# Buffers.net
KiCad netlist of a schematic drawn in Altium Designer
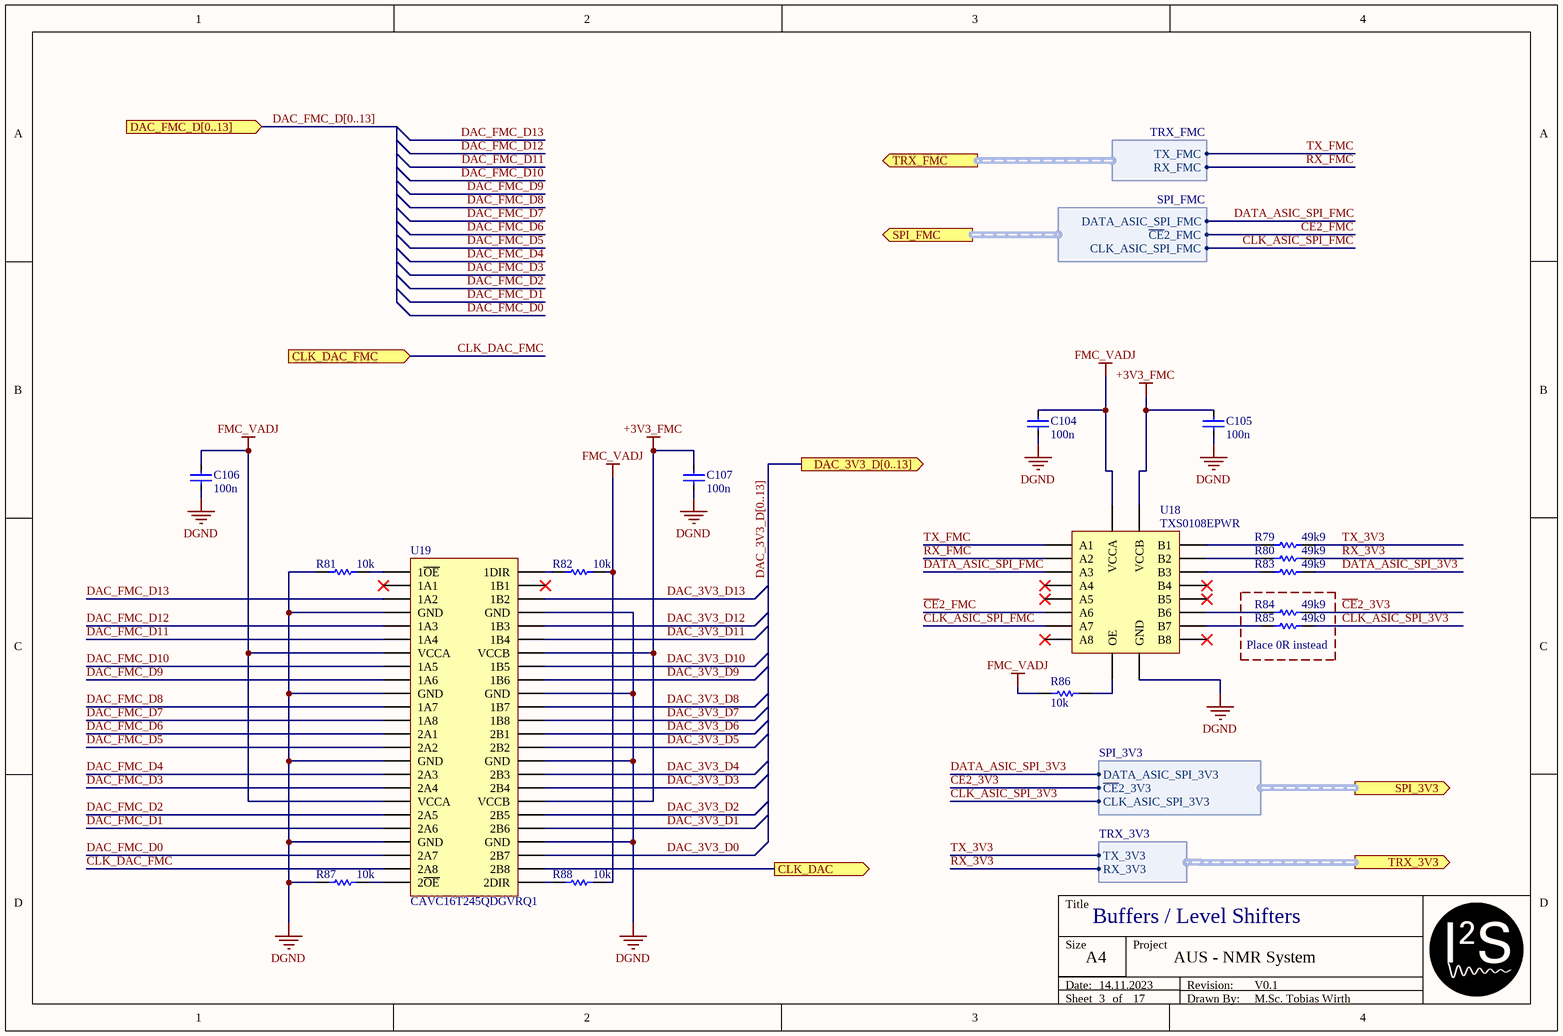
[diagram p0: Buffers.SchDoc]

(export (version "E")
  (design (tool "Eeschema 10.0.6"))
  (components
    (comp (ref "C104") (value "100n") (footprint "CAP_0402") (libsource (lib "IIS-Lib_TW") (part "Cap")))
    (comp (ref "C105") (value "100n") (footprint "CAP_0402") (libsource (lib "IIS-Lib_TW") (part "Cap")))
    (comp (ref "C106") (value "100n") (footprint "CAP_0402") (libsource (lib "IIS-Lib_TW") (part "Cap")))
    (comp (ref "C107") (value "100n") (footprint "CAP_0402") (libsource (lib "IIS-Lib_TW") (part "Cap")))
    (comp (ref "R79") (value "49k9") (footprint "RES_0402") (libsource (lib "IIS-Lib_TW") (part "Res")))
    (comp (ref "R80") (value "49k9") (footprint "RES_0402") (libsource (lib "IIS-Lib_TW") (part "Res")))
    (comp (ref "R81") (value "10k") (footprint "RES_0402") (libsource (lib "IIS-Lib_TW") (part "Res")))
    (comp (ref "R82") (value "10k") (footprint "RES_0402") (libsource (lib "IIS-Lib_TW") (part "Res")))
    (comp (ref "R83") (value "49k9") (footprint "RES_0402") (libsource (lib "IIS-Lib_TW") (part "Res")))
    (comp (ref "R84") (value "49k9") (footprint "RES_0402") (libsource (lib "IIS-Lib_TW") (part "Res")))
    (comp (ref "R85") (value "49k9") (footprint "RES_0402") (libsource (lib "IIS-Lib_TW") (part "Res")))
    (comp (ref "R86") (value "10k") (footprint "RES_0402") (libsource (lib "IIS-Lib_TW") (part "Res")))
    (comp (ref "R87") (value "10k") (footprint "RES_0402") (libsource (lib "IIS-Lib_TW") (part "Res")))
    (comp (ref "R88") (value "10k") (footprint "RES_0402") (libsource (lib "IIS-Lib_TW") (part "Res")))
    (comp (ref "U18")
      (value "TXS0108EPWR")
      (footprint "TSSOP-20")
      (description "8-Bit Bi-directional, Level-Shifting, Voltage Translator for Open-Drain and Push-Pull Applications")
      (libsource (lib "IIS-Lib_TW") (part "TXS0108EPWR"))
    )
    (comp (ref "U19")
      (value "CAVC16T245QDGVRQ1")
      (footprint "IIS-Lib_TW:TSSOP40P640X120-48N")
      (description "16-Bit Dual-Supply Bus Transceiver With Configurable Voltage Translation and 3-State Outputs")
      (libsource (lib "IIS-Lib_TW") (part "CAVC16T245QDGVRQ1"))
    )
  )
  (nets
    (net (code "5") (name "+3V3_FMC") (class "Default")
      (node (ref "C105") (pin "1") (pinfunction "1_1") (pintype "passive"))
      (node (ref "C107") (pin "1") (pinfunction "1_1") (pintype "passive"))
      (node (ref "U18") (pin "19") (pinfunction "VCCB_19") (pintype "passive"))
      (node (ref "U19") (pin "18") (pinfunction "VCCB_18") (pintype "passive"))
      (node (ref "U19") (pin "7") (pinfunction "VCCB_7") (pintype "passive"))
    )
    (net (code "6") (name "/CLK_ASIC_SPI_3V3") (class "Default")
      (node (ref "R85") (pin "2") (pinfunction "2_2") (pintype "passive"))
    )
    (net (code "7") (name "/CLK_ASIC_SPI_FMC") (class "Default")
      (node (ref "U18") (pin "8") (pinfunction "A7_8") (pintype "passive"))
    )
    (net (code "8") (name "/CLK_DAC") (class "Default")
      (node (ref "U19") (pin "23") (pinfunction "2B8_23") (pintype "passive"))
    )
    (net (code "9") (name "/CLK_DAC_FMC") (class "Default")
      (node (ref "U19") (pin "26") (pinfunction "2A8_26") (pintype "passive"))
    )
    (net (code "10") (name "/DAC_3V3_D0") (class "Default")
      (node (ref "U19") (pin "22") (pinfunction "2B7_22") (pintype "passive"))
    )
    (net (code "11") (name "/DAC_3V3_D1") (class "Default")
      (node (ref "U19") (pin "20") (pinfunction "2B6_20") (pintype "passive"))
    )
    (net (code "12") (name "/DAC_3V3_D2") (class "Default")
      (node (ref "U19") (pin "19") (pinfunction "2B5_19") (pintype "passive"))
    )
    (net (code "13") (name "/DAC_3V3_D3") (class "Default")
      (node (ref "U19") (pin "17") (pinfunction "2B4_17") (pintype "passive"))
    )
    (net (code "14") (name "/DAC_3V3_D4") (class "Default")
      (node (ref "U19") (pin "16") (pinfunction "2B3_16") (pintype "passive"))
    )
    (net (code "15") (name "/DAC_3V3_D5") (class "Default")
      (node (ref "U19") (pin "14") (pinfunction "2B2_14") (pintype "passive"))
    )
    (net (code "16") (name "/DAC_3V3_D6") (class "Default")
      (node (ref "U19") (pin "13") (pinfunction "2B1_13") (pintype "passive"))
    )
    (net (code "17") (name "/DAC_3V3_D7") (class "Default")
      (node (ref "U19") (pin "12") (pinfunction "1B8_12") (pintype "passive"))
    )
    (net (code "18") (name "/DAC_3V3_D8") (class "Default")
      (node (ref "U19") (pin "11") (pinfunction "1B7_11") (pintype "passive"))
    )
    (net (code "19") (name "/DAC_3V3_D9") (class "Default")
      (node (ref "U19") (pin "9") (pinfunction "1B6_9") (pintype "passive"))
    )
    (net (code "20") (name "/DAC_3V3_D10") (class "Default")
      (node (ref "U19") (pin "8") (pinfunction "1B5_8") (pintype "passive"))
    )
    (net (code "21") (name "/DAC_3V3_D11") (class "Default")
      (node (ref "U19") (pin "6") (pinfunction "1B4_6") (pintype "passive"))
    )
    (net (code "22") (name "/DAC_3V3_D12") (class "Default")
      (node (ref "U19") (pin "5") (pinfunction "1B3_5") (pintype "passive"))
    )
    (net (code "23") (name "/DAC_3V3_D13") (class "Default")
      (node (ref "U19") (pin "3") (pinfunction "1B2_3") (pintype "passive"))
    )
    (net (code "25") (name "/DAC_FMC_D0") (class "Default")
      (node (ref "U19") (pin "27") (pinfunction "2A7_27") (pintype "passive"))
    )
    (net (code "26") (name "/DAC_FMC_D1") (class "Default")
      (node (ref "U19") (pin "29") (pinfunction "2A6_29") (pintype "passive"))
    )
    (net (code "27") (name "/DAC_FMC_D2") (class "Default")
      (node (ref "U19") (pin "30") (pinfunction "2A5_30") (pintype "passive"))
    )
    (net (code "28") (name "/DAC_FMC_D3") (class "Default")
      (node (ref "U19") (pin "32") (pinfunction "2A4_32") (pintype "passive"))
    )
    (net (code "29") (name "/DAC_FMC_D4") (class "Default")
      (node (ref "U19") (pin "33") (pinfunction "2A3_33") (pintype "passive"))
    )
    (net (code "30") (name "/DAC_FMC_D5") (class "Default")
      (node (ref "U19") (pin "35") (pinfunction "2A2_35") (pintype "passive"))
    )
    (net (code "31") (name "/DAC_FMC_D6") (class "Default")
      (node (ref "U19") (pin "36") (pinfunction "2A1_36") (pintype "passive"))
    )
    (net (code "32") (name "/DAC_FMC_D7") (class "Default")
      (node (ref "U19") (pin "37") (pinfunction "1A8_37") (pintype "passive"))
    )
    (net (code "33") (name "/DAC_FMC_D8") (class "Default")
      (node (ref "U19") (pin "38") (pinfunction "1A7_38") (pintype "passive"))
    )
    (net (code "34") (name "/DAC_FMC_D9") (class "Default")
      (node (ref "U19") (pin "40") (pinfunction "1A6_40") (pintype "passive"))
    )
    (net (code "35") (name "/DAC_FMC_D10") (class "Default")
      (node (ref "U19") (pin "41") (pinfunction "1A5_41") (pintype "passive"))
    )
    (net (code "36") (name "/DAC_FMC_D11") (class "Default")
      (node (ref "U19") (pin "43") (pinfunction "1A4_43") (pintype "passive"))
    )
    (net (code "37") (name "/DAC_FMC_D12") (class "Default")
      (node (ref "U19") (pin "44") (pinfunction "1A3_44") (pintype "passive"))
    )
    (net (code "38") (name "/DAC_FMC_D13") (class "Default")
      (node (ref "U19") (pin "46") (pinfunction "1A2_46") (pintype "passive"))
    )
    (net (code "40") (name "/DATA_ASIC_SPI_3V3") (class "Default")
      (node (ref "R83") (pin "2") (pinfunction "2_2") (pintype "passive"))
    )
    (net (code "41") (name "/DATA_ASIC_SPI_FMC") (class "Default")
      (node (ref "U18") (pin "4") (pinfunction "A3_4") (pintype "passive"))
    )
    (net (code "42") (name "/RX_3V3") (class "Default")
      (node (ref "R80") (pin "2") (pinfunction "2_2") (pintype "passive"))
    )
    (net (code "43") (name "/RX_FMC") (class "Default")
      (node (ref "U18") (pin "3") (pinfunction "A2_3") (pintype "passive"))
    )
    (net (code "44") (name "/TX_3V3") (class "Default")
      (node (ref "R79") (pin "2") (pinfunction "2_2") (pintype "passive"))
    )
    (net (code "45") (name "/TX_FMC") (class "Default")
      (node (ref "U18") (pin "1") (pinfunction "A1_1") (pintype "passive"))
    )
    (net (code "50") (name "/~{CE}2_3V3") (class "Default")
      (node (ref "R84") (pin "2") (pinfunction "2_2") (pintype "passive"))
    )
    (net (code "51") (name "/~{CE}2_FMC") (class "Default")
      (node (ref "U18") (pin "7") (pinfunction "A6_7") (pintype "passive"))
    )
    (net (code "52") (name "DGND") (class "Default")
      (node (ref "C104") (pin "2") (pinfunction "2_2") (pintype "passive"))
      (node (ref "C105") (pin "2") (pinfunction "2_2") (pintype "passive"))
      (node (ref "C106") (pin "2") (pinfunction "2_2") (pintype "passive"))
      (node (ref "C107") (pin "2") (pinfunction "2_2") (pintype "passive"))
      (node (ref "R81") (pin "2") (pinfunction "2_2") (pintype "passive"))
      (node (ref "R87") (pin "2") (pinfunction "2_2") (pintype "passive"))
      (node (ref "U18") (pin "11") (pinfunction "GND_11") (pintype "passive"))
      (node (ref "U19") (pin "10") (pinfunction "GND_10") (pintype "passive"))
      (node (ref "U19") (pin "15") (pinfunction "GND_15") (pintype "passive"))
      (node (ref "U19") (pin "21") (pinfunction "GND_21") (pintype "passive"))
      (node (ref "U19") (pin "28") (pinfunction "GND_28") (pintype "passive"))
      (node (ref "U19") (pin "34") (pinfunction "GND_34") (pintype "passive"))
      (node (ref "U19") (pin "39") (pinfunction "GND_39") (pintype "passive"))
      (node (ref "U19") (pin "4") (pinfunction "GND_4") (pintype "passive"))
      (node (ref "U19") (pin "45") (pinfunction "GND_45") (pintype "passive"))
    )
    (net (code "53") (name "FMC_VADJ") (class "Default")
      (node (ref "C104") (pin "1") (pinfunction "1_1") (pintype "passive"))
      (node (ref "C106") (pin "1") (pinfunction "1_1") (pintype "passive"))
      (node (ref "R82") (pin "1") (pinfunction "1_1") (pintype "passive"))
      (node (ref "R86") (pin "2") (pinfunction "2_2") (pintype "passive"))
      (node (ref "R88") (pin "1") (pinfunction "1_1") (pintype "passive"))
      (node (ref "U18") (pin "2") (pinfunction "VCCA_2") (pintype "passive"))
      (node (ref "U19") (pin "31") (pinfunction "VCCA_31") (pintype "passive"))
      (node (ref "U19") (pin "42") (pinfunction "VCCA_42") (pintype "passive"))
    )
    (net (code "54") (name "Net-(U18-B1)") (class "Default")
      (node (ref "R79") (pin "1") (pinfunction "1_1") (pintype "passive"))
      (node (ref "U18") (pin "20") (pinfunction "B1_20") (pintype "passive"))
    )
    (net (code "55") (name "Net-(U18-B2)") (class "Default")
      (node (ref "R80") (pin "1") (pinfunction "1_1") (pintype "passive"))
      (node (ref "U18") (pin "18") (pinfunction "B2_18") (pintype "passive"))
    )
    (net (code "56") (name "Net-(U18-B3)") (class "Default")
      (node (ref "R83") (pin "1") (pinfunction "1_1") (pintype "passive"))
      (node (ref "U18") (pin "17") (pinfunction "B3_17") (pintype "passive"))
    )
    (net (code "57") (name "Net-(U18-B6)") (class "Default")
      (node (ref "R84") (pin "1") (pinfunction "1_1") (pintype "passive"))
      (node (ref "U18") (pin "14") (pinfunction "B6_14") (pintype "passive"))
    )
    (net (code "58") (name "Net-(U18-B7)") (class "Default")
      (node (ref "R85") (pin "1") (pinfunction "1_1") (pintype "passive"))
      (node (ref "U18") (pin "13") (pinfunction "B7_13") (pintype "passive"))
    )
    (net (code "59") (name "Net-(U18-OE)") (class "Default")
      (node (ref "R86") (pin "1") (pinfunction "1_1") (pintype "passive"))
      (node (ref "U18") (pin "10") (pinfunction "OE_10") (pintype "passive"))
    )
    (net (code "60") (name "Net-(U19-1DIR)") (class "Default")
      (node (ref "R82") (pin "2") (pinfunction "2_2") (pintype "passive"))
      (node (ref "U19") (pin "1") (pinfunction "1DIR_1") (pintype "passive"))
    )
    (net (code "61") (name "Net-(U19-1~{OE})") (class "Default")
      (node (ref "R81") (pin "1") (pinfunction "1_1") (pintype "passive"))
      (node (ref "U19") (pin "48") (pinfunction "1~{OE}_48") (pintype "passive"))
    )
    (net (code "62") (name "Net-(U19-2DIR)") (class "Default")
      (node (ref "R88") (pin "2") (pinfunction "2_2") (pintype "passive"))
      (node (ref "U19") (pin "24") (pinfunction "2DIR_24") (pintype "passive"))
    )
    (net (code "63") (name "Net-(U19-2~{OE})") (class "Default")
      (node (ref "R87") (pin "1") (pinfunction "1_1") (pintype "passive"))
      (node (ref "U19") (pin "25") (pinfunction "2~{OE}_25") (pintype "passive"))
    )
    (net (code "64") (name "unconnected-(U18-A4-Pad5)") (class "Default")
      (node (ref "U18") (pin "5") (pinfunction "A4_5") (pintype "passive+no_connect"))
    )
    (net (code "65") (name "unconnected-(U18-A5-Pad6)") (class "Default")
      (node (ref "U18") (pin "6") (pinfunction "A5_6") (pintype "passive+no_connect"))
    )
    (net (code "66") (name "unconnected-(U18-A8-Pad9)") (class "Default")
      (node (ref "U18") (pin "9") (pinfunction "A8_9") (pintype "passive+no_connect"))
    )
    (net (code "67") (name "unconnected-(U18-B4-Pad16)") (class "Default")
      (node (ref "U18") (pin "16") (pinfunction "B4_16") (pintype "passive+no_connect"))
    )
    (net (code "68") (name "unconnected-(U18-B5-Pad15)") (class "Default")
      (node (ref "U18") (pin "15") (pinfunction "B5_15") (pintype "passive+no_connect"))
    )
    (net (code "69") (name "unconnected-(U18-B8-Pad12)") (class "Default")
      (node (ref "U18") (pin "12") (pinfunction "B8_12") (pintype "passive+no_connect"))
    )
    (net (code "70") (name "unconnected-(U19-1A1-Pad47)") (class "Default")
      (node (ref "U19") (pin "47") (pinfunction "1A1_47") (pintype "passive+no_connect"))
    )
    (net (code "71") (name "unconnected-(U19-1B1-Pad2)") (class "Default")
      (node (ref "U19") (pin "2") (pinfunction "1B1_2") (pintype "passive+no_connect"))
    )
  )
)
